# Solar_LEDs.net
KiCad netlist of a schematic drawn in EAGLE
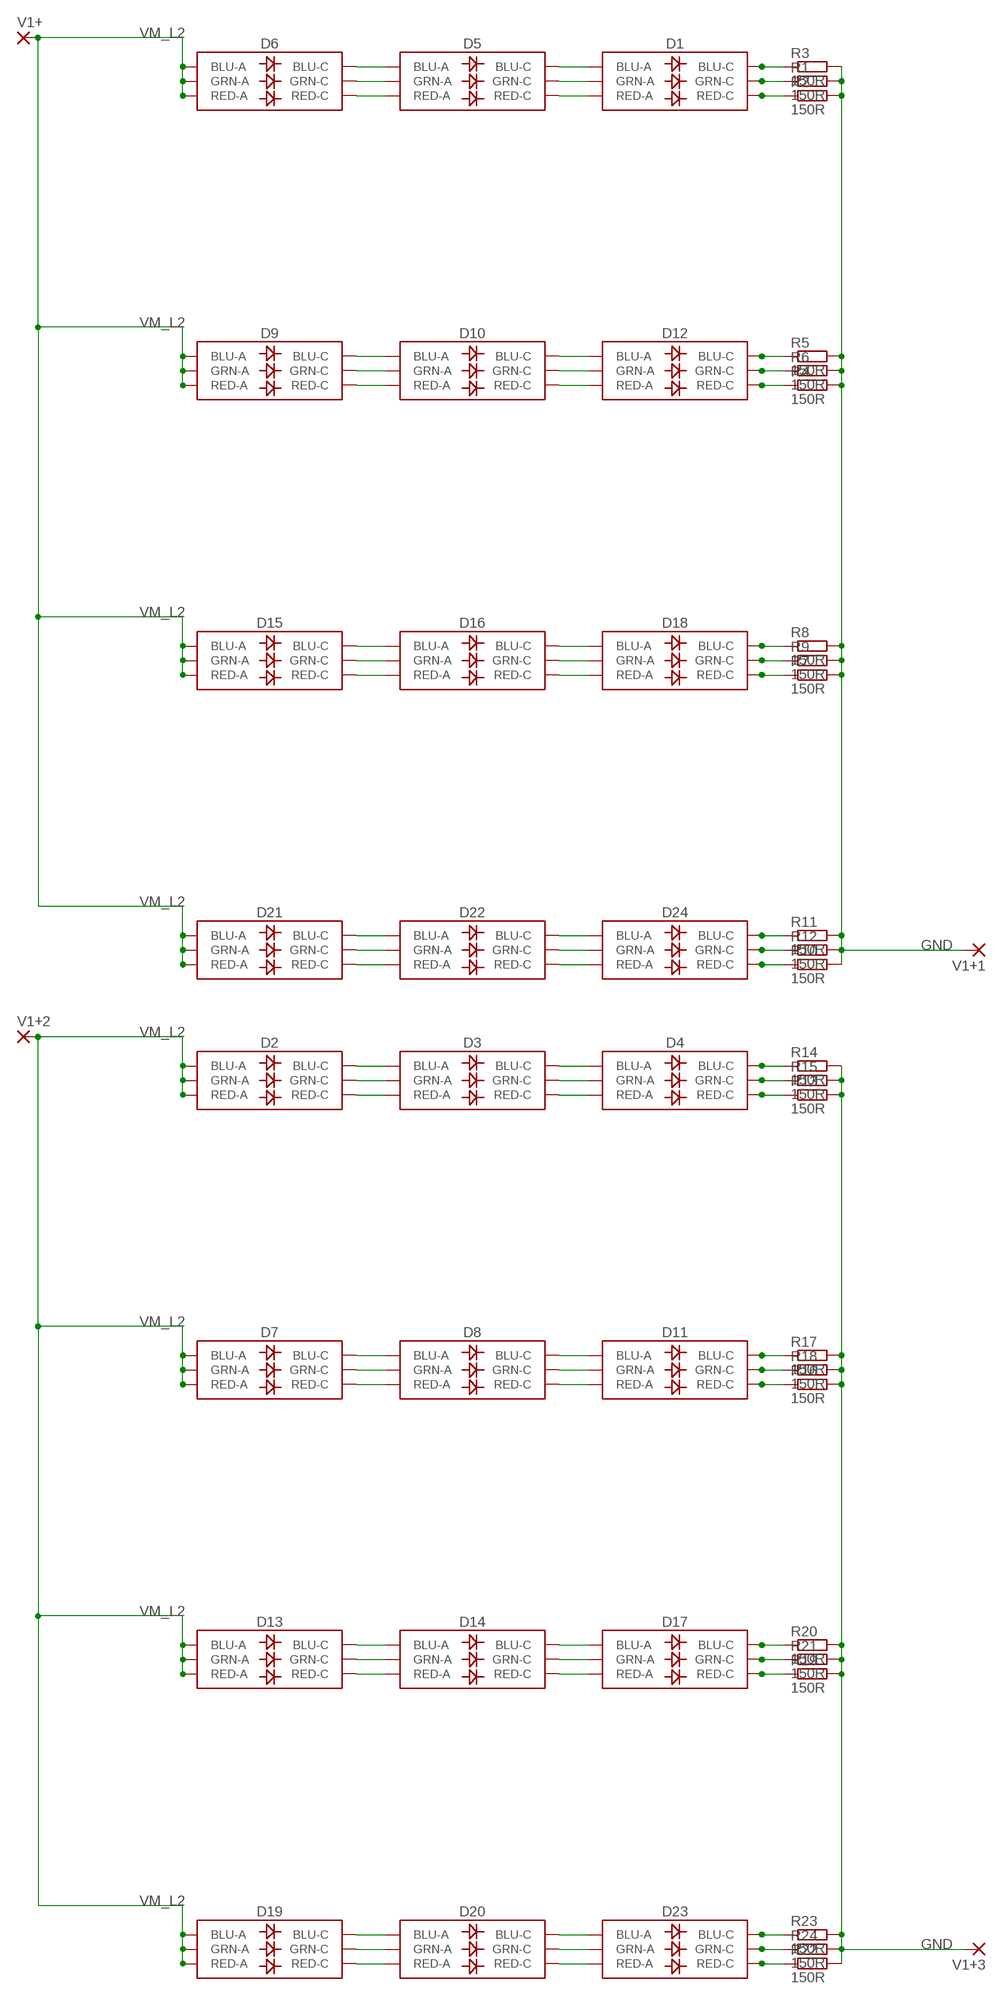
[diagram p0: schematic, sheet 1]

(export (version "E")
  (design (tool "Eeschema 10.0.6"))
  (components
    (comp (ref "D1")
      (value "LED-RGBNO_IC")
      (footprint "eagle-import:LED-TRICOLOR-5050")
      (libsource (lib "eagle-import") (part "LED-RGBNO_IC"))
    )
    (comp (ref "D2")
      (value "LED-RGBNO_IC")
      (footprint "eagle-import:LED-TRICOLOR-5050")
      (libsource (lib "eagle-import") (part "LED-RGBNO_IC"))
    )
    (comp (ref "D3")
      (value "LED-RGBNO_IC")
      (footprint "eagle-import:LED-TRICOLOR-5050")
      (libsource (lib "eagle-import") (part "LED-RGBNO_IC"))
    )
    (comp (ref "D4")
      (value "LED-RGBNO_IC")
      (footprint "eagle-import:LED-TRICOLOR-5050")
      (libsource (lib "eagle-import") (part "LED-RGBNO_IC"))
    )
    (comp (ref "D5")
      (value "LED-RGBNO_IC")
      (footprint "eagle-import:LED-TRICOLOR-5050")
      (libsource (lib "eagle-import") (part "LED-RGBNO_IC"))
    )
    (comp (ref "D6")
      (value "LED-RGBNO_IC")
      (footprint "eagle-import:LED-TRICOLOR-5050")
      (libsource (lib "eagle-import") (part "LED-RGBNO_IC"))
    )
    (comp (ref "D7")
      (value "LED-RGBNO_IC")
      (footprint "eagle-import:LED-TRICOLOR-5050")
      (libsource (lib "eagle-import") (part "LED-RGBNO_IC"))
    )
    (comp (ref "D8")
      (value "LED-RGBNO_IC")
      (footprint "eagle-import:LED-TRICOLOR-5050")
      (libsource (lib "eagle-import") (part "LED-RGBNO_IC"))
    )
    (comp (ref "D9")
      (value "LED-RGBNO_IC")
      (footprint "eagle-import:LED-TRICOLOR-5050")
      (libsource (lib "eagle-import") (part "LED-RGBNO_IC"))
    )
    (comp (ref "D10")
      (value "LED-RGBNO_IC")
      (footprint "eagle-import:LED-TRICOLOR-5050")
      (libsource (lib "eagle-import") (part "LED-RGBNO_IC"))
    )
    (comp (ref "D11")
      (value "LED-RGBNO_IC")
      (footprint "eagle-import:LED-TRICOLOR-5050")
      (libsource (lib "eagle-import") (part "LED-RGBNO_IC"))
    )
    (comp (ref "D12")
      (value "LED-RGBNO_IC")
      (footprint "eagle-import:LED-TRICOLOR-5050")
      (libsource (lib "eagle-import") (part "LED-RGBNO_IC"))
    )
    (comp (ref "D13")
      (value "LED-RGBNO_IC")
      (footprint "eagle-import:LED-TRICOLOR-5050")
      (libsource (lib "eagle-import") (part "LED-RGBNO_IC"))
    )
    (comp (ref "D14")
      (value "LED-RGBNO_IC")
      (footprint "eagle-import:LED-TRICOLOR-5050")
      (libsource (lib "eagle-import") (part "LED-RGBNO_IC"))
    )
    (comp (ref "D15")
      (value "LED-RGBNO_IC")
      (footprint "eagle-import:LED-TRICOLOR-5050")
      (libsource (lib "eagle-import") (part "LED-RGBNO_IC"))
    )
    (comp (ref "D16")
      (value "LED-RGBNO_IC")
      (footprint "eagle-import:LED-TRICOLOR-5050")
      (libsource (lib "eagle-import") (part "LED-RGBNO_IC"))
    )
    (comp (ref "D17")
      (value "LED-RGBNO_IC")
      (footprint "eagle-import:LED-TRICOLOR-5050")
      (libsource (lib "eagle-import") (part "LED-RGBNO_IC"))
    )
    (comp (ref "D18")
      (value "LED-RGBNO_IC")
      (footprint "eagle-import:LED-TRICOLOR-5050")
      (libsource (lib "eagle-import") (part "LED-RGBNO_IC"))
    )
    (comp (ref "D19")
      (value "LED-RGBNO_IC")
      (footprint "eagle-import:LED-TRICOLOR-5050")
      (libsource (lib "eagle-import") (part "LED-RGBNO_IC"))
    )
    (comp (ref "D20")
      (value "LED-RGBNO_IC")
      (footprint "eagle-import:LED-TRICOLOR-5050")
      (libsource (lib "eagle-import") (part "LED-RGBNO_IC"))
    )
    (comp (ref "D21")
      (value "LED-RGBNO_IC")
      (footprint "eagle-import:LED-TRICOLOR-5050")
      (libsource (lib "eagle-import") (part "LED-RGBNO_IC"))
    )
    (comp (ref "D22")
      (value "LED-RGBNO_IC")
      (footprint "eagle-import:LED-TRICOLOR-5050")
      (libsource (lib "eagle-import") (part "LED-RGBNO_IC"))
    )
    (comp (ref "D23")
      (value "LED-RGBNO_IC")
      (footprint "eagle-import:LED-TRICOLOR-5050")
      (libsource (lib "eagle-import") (part "LED-RGBNO_IC"))
    )
    (comp (ref "D24")
      (value "LED-RGBNO_IC")
      (footprint "eagle-import:LED-TRICOLOR-5050")
      (libsource (lib "eagle-import") (part "LED-RGBNO_IC"))
    )
    (comp (ref "R1")
      (value "150R")
      (footprint "eagle-import:M1206")
      (libsource (lib "eagle-import") (part "R-EU_M1206"))
    )
    (comp (ref "R2")
      (value "150R")
      (footprint "eagle-import:M1206")
      (libsource (lib "eagle-import") (part "R-EU_M1206"))
    )
    (comp (ref "R3")
      (value "150R")
      (footprint "eagle-import:M1206")
      (libsource (lib "eagle-import") (part "R-EU_M1206"))
    )
    (comp (ref "R4")
      (value "150R")
      (footprint "eagle-import:M1206")
      (libsource (lib "eagle-import") (part "R-EU_M1206"))
    )
    (comp (ref "R5")
      (value "150R")
      (footprint "eagle-import:M1206")
      (libsource (lib "eagle-import") (part "R-EU_M1206"))
    )
    (comp (ref "R6")
      (value "150R")
      (footprint "eagle-import:M1206")
      (libsource (lib "eagle-import") (part "R-EU_M1206"))
    )
    (comp (ref "R7")
      (value "150R")
      (footprint "eagle-import:M1206")
      (libsource (lib "eagle-import") (part "R-EU_M1206"))
    )
    (comp (ref "R8")
      (value "150R")
      (footprint "eagle-import:M1206")
      (libsource (lib "eagle-import") (part "R-EU_M1206"))
    )
    (comp (ref "R9")
      (value "150R")
      (footprint "eagle-import:M1206")
      (libsource (lib "eagle-import") (part "R-EU_M1206"))
    )
    (comp (ref "R10")
      (value "150R")
      (footprint "eagle-import:M1206")
      (libsource (lib "eagle-import") (part "R-EU_M1206"))
    )
    (comp (ref "R11")
      (value "150R")
      (footprint "eagle-import:M1206")
      (libsource (lib "eagle-import") (part "R-EU_M1206"))
    )
    (comp (ref "R12")
      (value "150R")
      (footprint "eagle-import:M1206")
      (libsource (lib "eagle-import") (part "R-EU_M1206"))
    )
    (comp (ref "R13")
      (value "150R")
      (footprint "eagle-import:M1206")
      (libsource (lib "eagle-import") (part "R-EU_M1206"))
    )
    (comp (ref "R14")
      (value "150R")
      (footprint "eagle-import:M1206")
      (libsource (lib "eagle-import") (part "R-EU_M1206"))
    )
    (comp (ref "R15")
      (value "150R")
      (footprint "eagle-import:M1206")
      (libsource (lib "eagle-import") (part "R-EU_M1206"))
    )
    (comp (ref "R16")
      (value "150R")
      (footprint "eagle-import:M1206")
      (libsource (lib "eagle-import") (part "R-EU_M1206"))
    )
    (comp (ref "R17")
      (value "150R")
      (footprint "eagle-import:M1206")
      (libsource (lib "eagle-import") (part "R-EU_M1206"))
    )
    (comp (ref "R18")
      (value "150R")
      (footprint "eagle-import:M1206")
      (libsource (lib "eagle-import") (part "R-EU_M1206"))
    )
    (comp (ref "R19")
      (value "150R")
      (footprint "eagle-import:M1206")
      (libsource (lib "eagle-import") (part "R-EU_M1206"))
    )
    (comp (ref "R20")
      (value "150R")
      (footprint "eagle-import:M1206")
      (libsource (lib "eagle-import") (part "R-EU_M1206"))
    )
    (comp (ref "R21")
      (value "150R")
      (footprint "eagle-import:M1206")
      (libsource (lib "eagle-import") (part "R-EU_M1206"))
    )
    (comp (ref "R22")
      (value "150R")
      (footprint "eagle-import:M1206")
      (libsource (lib "eagle-import") (part "R-EU_M1206"))
    )
    (comp (ref "R23")
      (value "150R")
      (footprint "eagle-import:M1206")
      (libsource (lib "eagle-import") (part "R-EU_M1206"))
    )
    (comp (ref "R24")
      (value "150R")
      (footprint "eagle-import:M1206")
      (libsource (lib "eagle-import") (part "R-EU_M1206"))
    )
    (comp (ref "V1+")
      (value "2,54/1,0")
      (footprint "eagle-import:2,54_1,0")
      (libsource (lib "eagle-import") (part "2,54/1,0"))
    )
    (comp (ref "V1+1")
      (value "2,54/1,0")
      (footprint "eagle-import:2,54_1,0")
      (libsource (lib "eagle-import") (part "2,54/1,0"))
    )
    (comp (ref "V1+2")
      (value "2,54/1,0")
      (footprint "eagle-import:2,54_1,0")
      (libsource (lib "eagle-import") (part "2,54/1,0"))
    )
    (comp (ref "V1+3")
      (value "2,54/1,0")
      (footprint "eagle-import:2,54_1,0")
      (libsource (lib "eagle-import") (part "2,54/1,0"))
    )
  )
  (nets
    (net (code "1") (name "/GND") (class "Default")
      (node (ref "R1") (pin "2") (pinfunction "2_2") (pintype "passive"))
      (node (ref "R10") (pin "2") (pinfunction "2_2") (pintype "passive"))
      (node (ref "R11") (pin "2") (pinfunction "2_2") (pintype "passive"))
      (node (ref "R12") (pin "2") (pinfunction "2_2") (pintype "passive"))
      (node (ref "R13") (pin "2") (pinfunction "2_2") (pintype "passive"))
      (node (ref "R14") (pin "2") (pinfunction "2_2") (pintype "passive"))
      (node (ref "R15") (pin "2") (pinfunction "2_2") (pintype "passive"))
      (node (ref "R16") (pin "2") (pinfunction "2_2") (pintype "passive"))
      (node (ref "R17") (pin "2") (pinfunction "2_2") (pintype "passive"))
      (node (ref "R18") (pin "2") (pinfunction "2_2") (pintype "passive"))
      (node (ref "R19") (pin "2") (pinfunction "2_2") (pintype "passive"))
      (node (ref "R2") (pin "2") (pinfunction "2_2") (pintype "passive"))
      (node (ref "R20") (pin "2") (pinfunction "2_2") (pintype "passive"))
      (node (ref "R21") (pin "2") (pinfunction "2_2") (pintype "passive"))
      (node (ref "R22") (pin "2") (pinfunction "2_2") (pintype "passive"))
      (node (ref "R23") (pin "2") (pinfunction "2_2") (pintype "passive"))
      (node (ref "R24") (pin "2") (pinfunction "2_2") (pintype "passive"))
      (node (ref "R3") (pin "2") (pinfunction "2_2") (pintype "passive"))
      (node (ref "R4") (pin "2") (pinfunction "2_2") (pintype "passive"))
      (node (ref "R5") (pin "2") (pinfunction "2_2") (pintype "passive"))
      (node (ref "R6") (pin "2") (pinfunction "2_2") (pintype "passive"))
      (node (ref "R7") (pin "2") (pinfunction "2_2") (pintype "passive"))
      (node (ref "R8") (pin "2") (pinfunction "2_2") (pintype "passive"))
      (node (ref "R9") (pin "2") (pinfunction "2_2") (pintype "passive"))
      (node (ref "V1+1") (pin "1") (pinfunction "P_1") (pintype "passive"))
      (node (ref "V1+3") (pin "1") (pinfunction "P_1") (pintype "passive"))
    )
    (net (code "2") (name "/VM_L2") (class "Default")
      (node (ref "D13") (pin "1") (pinfunction "GRN-A_1") (pintype "bidirectional"))
      (node (ref "D13") (pin "2") (pinfunction "RED-A_2") (pintype "bidirectional"))
      (node (ref "D13") (pin "3") (pinfunction "BLU-A_3") (pintype "bidirectional"))
      (node (ref "D15") (pin "1") (pinfunction "GRN-A_1") (pintype "bidirectional"))
      (node (ref "D15") (pin "2") (pinfunction "RED-A_2") (pintype "bidirectional"))
      (node (ref "D15") (pin "3") (pinfunction "BLU-A_3") (pintype "bidirectional"))
      (node (ref "D19") (pin "1") (pinfunction "GRN-A_1") (pintype "bidirectional"))
      (node (ref "D19") (pin "2") (pinfunction "RED-A_2") (pintype "bidirectional"))
      (node (ref "D19") (pin "3") (pinfunction "BLU-A_3") (pintype "bidirectional"))
      (node (ref "D2") (pin "1") (pinfunction "GRN-A_1") (pintype "bidirectional"))
      (node (ref "D2") (pin "2") (pinfunction "RED-A_2") (pintype "bidirectional"))
      (node (ref "D2") (pin "3") (pinfunction "BLU-A_3") (pintype "bidirectional"))
      (node (ref "D21") (pin "1") (pinfunction "GRN-A_1") (pintype "bidirectional"))
      (node (ref "D21") (pin "2") (pinfunction "RED-A_2") (pintype "bidirectional"))
      (node (ref "D21") (pin "3") (pinfunction "BLU-A_3") (pintype "bidirectional"))
      (node (ref "D6") (pin "1") (pinfunction "GRN-A_1") (pintype "bidirectional"))
      (node (ref "D6") (pin "2") (pinfunction "RED-A_2") (pintype "bidirectional"))
      (node (ref "D6") (pin "3") (pinfunction "BLU-A_3") (pintype "bidirectional"))
      (node (ref "D7") (pin "1") (pinfunction "GRN-A_1") (pintype "bidirectional"))
      (node (ref "D7") (pin "2") (pinfunction "RED-A_2") (pintype "bidirectional"))
      (node (ref "D7") (pin "3") (pinfunction "BLU-A_3") (pintype "bidirectional"))
      (node (ref "D9") (pin "1") (pinfunction "GRN-A_1") (pintype "bidirectional"))
      (node (ref "D9") (pin "2") (pinfunction "RED-A_2") (pintype "bidirectional"))
      (node (ref "D9") (pin "3") (pinfunction "BLU-A_3") (pintype "bidirectional"))
      (node (ref "V1+") (pin "1") (pinfunction "P_1") (pintype "passive"))
      (node (ref "V1+2") (pin "1") (pinfunction "P_1") (pintype "passive"))
    )
    (net (code "3") (name "Net-(D1-BLU-A)") (class "Default")
      (node (ref "D1") (pin "3") (pinfunction "BLU-A_3") (pintype "bidirectional"))
      (node (ref "D5") (pin "4") (pinfunction "BLU-C_4") (pintype "bidirectional"))
    )
    (net (code "4") (name "Net-(D1-BLU-C)") (class "Default")
      (node (ref "D1") (pin "4") (pinfunction "BLU-C_4") (pintype "bidirectional"))
      (node (ref "R3") (pin "1") (pinfunction "1_1") (pintype "passive"))
    )
    (net (code "5") (name "Net-(D1-GRN-A)") (class "Default")
      (node (ref "D1") (pin "1") (pinfunction "GRN-A_1") (pintype "bidirectional"))
      (node (ref "D5") (pin "6") (pinfunction "GRN-C_6") (pintype "bidirectional"))
    )
    (net (code "6") (name "Net-(D1-GRN-C)") (class "Default")
      (node (ref "D1") (pin "6") (pinfunction "GRN-C_6") (pintype "bidirectional"))
      (node (ref "R1") (pin "1") (pinfunction "1_1") (pintype "passive"))
    )
    (net (code "7") (name "Net-(D1-RED-A)") (class "Default")
      (node (ref "D1") (pin "2") (pinfunction "RED-A_2") (pintype "bidirectional"))
      (node (ref "D5") (pin "5") (pinfunction "RED-C_5") (pintype "bidirectional"))
    )
    (net (code "8") (name "Net-(D1-RED-C)") (class "Default")
      (node (ref "D1") (pin "5") (pinfunction "RED-C_5") (pintype "bidirectional"))
      (node (ref "R2") (pin "1") (pinfunction "1_1") (pintype "passive"))
    )
    (net (code "9") (name "Net-(D2-BLU-C)") (class "Default")
      (node (ref "D2") (pin "4") (pinfunction "BLU-C_4") (pintype "bidirectional"))
      (node (ref "D3") (pin "3") (pinfunction "BLU-A_3") (pintype "bidirectional"))
    )
    (net (code "10") (name "Net-(D2-GRN-C)") (class "Default")
      (node (ref "D2") (pin "6") (pinfunction "GRN-C_6") (pintype "bidirectional"))
      (node (ref "D3") (pin "1") (pinfunction "GRN-A_1") (pintype "bidirectional"))
    )
    (net (code "11") (name "Net-(D2-RED-C)") (class "Default")
      (node (ref "D2") (pin "5") (pinfunction "RED-C_5") (pintype "bidirectional"))
      (node (ref "D3") (pin "2") (pinfunction "RED-A_2") (pintype "bidirectional"))
    )
    (net (code "12") (name "Net-(D3-BLU-C)") (class "Default")
      (node (ref "D3") (pin "4") (pinfunction "BLU-C_4") (pintype "bidirectional"))
      (node (ref "D4") (pin "3") (pinfunction "BLU-A_3") (pintype "bidirectional"))
    )
    (net (code "13") (name "Net-(D3-GRN-C)") (class "Default")
      (node (ref "D3") (pin "6") (pinfunction "GRN-C_6") (pintype "bidirectional"))
      (node (ref "D4") (pin "1") (pinfunction "GRN-A_1") (pintype "bidirectional"))
    )
    (net (code "14") (name "Net-(D3-RED-C)") (class "Default")
      (node (ref "D3") (pin "5") (pinfunction "RED-C_5") (pintype "bidirectional"))
      (node (ref "D4") (pin "2") (pinfunction "RED-A_2") (pintype "bidirectional"))
    )
    (net (code "15") (name "Net-(D4-BLU-C)") (class "Default")
      (node (ref "D4") (pin "4") (pinfunction "BLU-C_4") (pintype "bidirectional"))
      (node (ref "R14") (pin "1") (pinfunction "1_1") (pintype "passive"))
    )
    (net (code "16") (name "Net-(D4-GRN-C)") (class "Default")
      (node (ref "D4") (pin "6") (pinfunction "GRN-C_6") (pintype "bidirectional"))
      (node (ref "R15") (pin "1") (pinfunction "1_1") (pintype "passive"))
    )
    (net (code "17") (name "Net-(D4-RED-C)") (class "Default")
      (node (ref "D4") (pin "5") (pinfunction "RED-C_5") (pintype "bidirectional"))
      (node (ref "R13") (pin "1") (pinfunction "1_1") (pintype "passive"))
    )
    (net (code "18") (name "Net-(D5-BLU-A)") (class "Default")
      (node (ref "D5") (pin "3") (pinfunction "BLU-A_3") (pintype "bidirectional"))
      (node (ref "D6") (pin "4") (pinfunction "BLU-C_4") (pintype "bidirectional"))
    )
    (net (code "19") (name "Net-(D5-GRN-A)") (class "Default")
      (node (ref "D5") (pin "1") (pinfunction "GRN-A_1") (pintype "bidirectional"))
      (node (ref "D6") (pin "6") (pinfunction "GRN-C_6") (pintype "bidirectional"))
    )
    (net (code "20") (name "Net-(D5-RED-A)") (class "Default")
      (node (ref "D5") (pin "2") (pinfunction "RED-A_2") (pintype "bidirectional"))
      (node (ref "D6") (pin "5") (pinfunction "RED-C_5") (pintype "bidirectional"))
    )
    (net (code "21") (name "Net-(D7-BLU-C)") (class "Default")
      (node (ref "D7") (pin "4") (pinfunction "BLU-C_4") (pintype "bidirectional"))
      (node (ref "D8") (pin "3") (pinfunction "BLU-A_3") (pintype "bidirectional"))
    )
    (net (code "22") (name "Net-(D7-GRN-C)") (class "Default")
      (node (ref "D7") (pin "6") (pinfunction "GRN-C_6") (pintype "bidirectional"))
      (node (ref "D8") (pin "1") (pinfunction "GRN-A_1") (pintype "bidirectional"))
    )
    (net (code "23") (name "Net-(D7-RED-C)") (class "Default")
      (node (ref "D7") (pin "5") (pinfunction "RED-C_5") (pintype "bidirectional"))
      (node (ref "D8") (pin "2") (pinfunction "RED-A_2") (pintype "bidirectional"))
    )
    (net (code "24") (name "Net-(D10-BLU-A)") (class "Default")
      (node (ref "D10") (pin "3") (pinfunction "BLU-A_3") (pintype "bidirectional"))
      (node (ref "D9") (pin "4") (pinfunction "BLU-C_4") (pintype "bidirectional"))
    )
    (net (code "25") (name "Net-(D10-BLU-C)") (class "Default")
      (node (ref "D10") (pin "4") (pinfunction "BLU-C_4") (pintype "bidirectional"))
      (node (ref "D12") (pin "3") (pinfunction "BLU-A_3") (pintype "bidirectional"))
    )
    (net (code "26") (name "Net-(D10-GRN-A)") (class "Default")
      (node (ref "D10") (pin "1") (pinfunction "GRN-A_1") (pintype "bidirectional"))
      (node (ref "D9") (pin "6") (pinfunction "GRN-C_6") (pintype "bidirectional"))
    )
    (net (code "27") (name "Net-(D10-GRN-C)") (class "Default")
      (node (ref "D10") (pin "6") (pinfunction "GRN-C_6") (pintype "bidirectional"))
      (node (ref "D12") (pin "1") (pinfunction "GRN-A_1") (pintype "bidirectional"))
    )
    (net (code "28") (name "Net-(D10-RED-A)") (class "Default")
      (node (ref "D10") (pin "2") (pinfunction "RED-A_2") (pintype "bidirectional"))
      (node (ref "D9") (pin "5") (pinfunction "RED-C_5") (pintype "bidirectional"))
    )
    (net (code "29") (name "Net-(D10-RED-C)") (class "Default")
      (node (ref "D10") (pin "5") (pinfunction "RED-C_5") (pintype "bidirectional"))
      (node (ref "D12") (pin "2") (pinfunction "RED-A_2") (pintype "bidirectional"))
    )
    (net (code "30") (name "Net-(D11-BLU-A)") (class "Default")
      (node (ref "D11") (pin "3") (pinfunction "BLU-A_3") (pintype "bidirectional"))
      (node (ref "D8") (pin "4") (pinfunction "BLU-C_4") (pintype "bidirectional"))
    )
    (net (code "31") (name "Net-(D11-BLU-C)") (class "Default")
      (node (ref "D11") (pin "4") (pinfunction "BLU-C_4") (pintype "bidirectional"))
      (node (ref "R17") (pin "1") (pinfunction "1_1") (pintype "passive"))
    )
    (net (code "32") (name "Net-(D11-GRN-A)") (class "Default")
      (node (ref "D11") (pin "1") (pinfunction "GRN-A_1") (pintype "bidirectional"))
      (node (ref "D8") (pin "6") (pinfunction "GRN-C_6") (pintype "bidirectional"))
    )
    (net (code "33") (name "Net-(D11-GRN-C)") (class "Default")
      (node (ref "D11") (pin "6") (pinfunction "GRN-C_6") (pintype "bidirectional"))
      (node (ref "R18") (pin "1") (pinfunction "1_1") (pintype "passive"))
    )
    (net (code "34") (name "Net-(D11-RED-A)") (class "Default")
      (node (ref "D11") (pin "2") (pinfunction "RED-A_2") (pintype "bidirectional"))
      (node (ref "D8") (pin "5") (pinfunction "RED-C_5") (pintype "bidirectional"))
    )
    (net (code "35") (name "Net-(D11-RED-C)") (class "Default")
      (node (ref "D11") (pin "5") (pinfunction "RED-C_5") (pintype "bidirectional"))
      (node (ref "R16") (pin "1") (pinfunction "1_1") (pintype "passive"))
    )
    (net (code "36") (name "Net-(D12-BLU-C)") (class "Default")
      (node (ref "D12") (pin "4") (pinfunction "BLU-C_4") (pintype "bidirectional"))
      (node (ref "R5") (pin "1") (pinfunction "1_1") (pintype "passive"))
    )
    (net (code "37") (name "Net-(D12-GRN-C)") (class "Default")
      (node (ref "D12") (pin "6") (pinfunction "GRN-C_6") (pintype "bidirectional"))
      (node (ref "R6") (pin "1") (pinfunction "1_1") (pintype "passive"))
    )
    (net (code "38") (name "Net-(D12-RED-C)") (class "Default")
      (node (ref "D12") (pin "5") (pinfunction "RED-C_5") (pintype "bidirectional"))
      (node (ref "R4") (pin "1") (pinfunction "1_1") (pintype "passive"))
    )
    (net (code "39") (name "Net-(D13-BLU-C)") (class "Default")
      (node (ref "D13") (pin "4") (pinfunction "BLU-C_4") (pintype "bidirectional"))
      (node (ref "D14") (pin "3") (pinfunction "BLU-A_3") (pintype "bidirectional"))
    )
    (net (code "40") (name "Net-(D13-GRN-C)") (class "Default")
      (node (ref "D13") (pin "6") (pinfunction "GRN-C_6") (pintype "bidirectional"))
      (node (ref "D14") (pin "1") (pinfunction "GRN-A_1") (pintype "bidirectional"))
    )
    (net (code "41") (name "Net-(D13-RED-C)") (class "Default")
      (node (ref "D13") (pin "5") (pinfunction "RED-C_5") (pintype "bidirectional"))
      (node (ref "D14") (pin "2") (pinfunction "RED-A_2") (pintype "bidirectional"))
    )
    (net (code "42") (name "Net-(D14-BLU-C)") (class "Default")
      (node (ref "D14") (pin "4") (pinfunction "BLU-C_4") (pintype "bidirectional"))
      (node (ref "D17") (pin "3") (pinfunction "BLU-A_3") (pintype "bidirectional"))
    )
    (net (code "43") (name "Net-(D14-GRN-C)") (class "Default")
      (node (ref "D14") (pin "6") (pinfunction "GRN-C_6") (pintype "bidirectional"))
      (node (ref "D17") (pin "1") (pinfunction "GRN-A_1") (pintype "bidirectional"))
    )
    (net (code "44") (name "Net-(D14-RED-C)") (class "Default")
      (node (ref "D14") (pin "5") (pinfunction "RED-C_5") (pintype "bidirectional"))
      (node (ref "D17") (pin "2") (pinfunction "RED-A_2") (pintype "bidirectional"))
    )
    (net (code "45") (name "Net-(D15-BLU-C)") (class "Default")
      (node (ref "D15") (pin "4") (pinfunction "BLU-C_4") (pintype "bidirectional"))
      (node (ref "D16") (pin "3") (pinfunction "BLU-A_3") (pintype "bidirectional"))
    )
    (net (code "46") (name "Net-(D15-GRN-C)") (class "Default")
      (node (ref "D15") (pin "6") (pinfunction "GRN-C_6") (pintype "bidirectional"))
      (node (ref "D16") (pin "1") (pinfunction "GRN-A_1") (pintype "bidirectional"))
    )
    (net (code "47") (name "Net-(D15-RED-C)") (class "Default")
      (node (ref "D15") (pin "5") (pinfunction "RED-C_5") (pintype "bidirectional"))
      (node (ref "D16") (pin "2") (pinfunction "RED-A_2") (pintype "bidirectional"))
    )
    (net (code "48") (name "Net-(D16-BLU-C)") (class "Default")
      (node (ref "D16") (pin "4") (pinfunction "BLU-C_4") (pintype "bidirectional"))
      (node (ref "D18") (pin "3") (pinfunction "BLU-A_3") (pintype "bidirectional"))
    )
    (net (code "49") (name "Net-(D16-GRN-C)") (class "Default")
      (node (ref "D16") (pin "6") (pinfunction "GRN-C_6") (pintype "bidirectional"))
      (node (ref "D18") (pin "1") (pinfunction "GRN-A_1") (pintype "bidirectional"))
    )
    (net (code "50") (name "Net-(D16-RED-C)") (class "Default")
      (node (ref "D16") (pin "5") (pinfunction "RED-C_5") (pintype "bidirectional"))
      (node (ref "D18") (pin "2") (pinfunction "RED-A_2") (pintype "bidirectional"))
    )
    (net (code "51") (name "Net-(D17-BLU-C)") (class "Default")
      (node (ref "D17") (pin "4") (pinfunction "BLU-C_4") (pintype "bidirectional"))
      (node (ref "R20") (pin "1") (pinfunction "1_1") (pintype "passive"))
    )
    (net (code "52") (name "Net-(D17-GRN-C)") (class "Default")
      (node (ref "D17") (pin "6") (pinfunction "GRN-C_6") (pintype "bidirectional"))
      (node (ref "R21") (pin "1") (pinfunction "1_1") (pintype "passive"))
    )
    (net (code "53") (name "Net-(D17-RED-C)") (class "Default")
      (node (ref "D17") (pin "5") (pinfunction "RED-C_5") (pintype "bidirectional"))
      (node (ref "R19") (pin "1") (pinfunction "1_1") (pintype "passive"))
    )
    (net (code "54") (name "Net-(D18-BLU-C)") (class "Default")
      (node (ref "D18") (pin "4") (pinfunction "BLU-C_4") (pintype "bidirectional"))
      (node (ref "R8") (pin "1") (pinfunction "1_1") (pintype "passive"))
    )
    (net (code "55") (name "Net-(D18-GRN-C)") (class "Default")
      (node (ref "D18") (pin "6") (pinfunction "GRN-C_6") (pintype "bidirectional"))
      (node (ref "R9") (pin "1") (pinfunction "1_1") (pintype "passive"))
    )
    (net (code "56") (name "Net-(D18-RED-C)") (class "Default")
      (node (ref "D18") (pin "5") (pinfunction "RED-C_5") (pintype "bidirectional"))
      (node (ref "R7") (pin "1") (pinfunction "1_1") (pintype "passive"))
    )
    (net (code "57") (name "Net-(D19-BLU-C)") (class "Default")
      (node (ref "D19") (pin "4") (pinfunction "BLU-C_4") (pintype "bidirectional"))
      (node (ref "D20") (pin "3") (pinfunction "BLU-A_3") (pintype "bidirectional"))
    )
    (net (code "58") (name "Net-(D19-GRN-C)") (class "Default")
      (node (ref "D19") (pin "6") (pinfunction "GRN-C_6") (pintype "bidirectional"))
      (node (ref "D20") (pin "1") (pinfunction "GRN-A_1") (pintype "bidirectional"))
    )
    (net (code "59") (name "Net-(D19-RED-C)") (class "Default")
      (node (ref "D19") (pin "5") (pinfunction "RED-C_5") (pintype "bidirectional"))
      (node (ref "D20") (pin "2") (pinfunction "RED-A_2") (pintype "bidirectional"))
    )
    (net (code "60") (name "Net-(D20-BLU-C)") (class "Default")
      (node (ref "D20") (pin "4") (pinfunction "BLU-C_4") (pintype "bidirectional"))
      (node (ref "D23") (pin "3") (pinfunction "BLU-A_3") (pintype "bidirectional"))
    )
    (net (code "61") (name "Net-(D20-GRN-C)") (class "Default")
      (node (ref "D20") (pin "6") (pinfunction "GRN-C_6") (pintype "bidirectional"))
      (node (ref "D23") (pin "1") (pinfunction "GRN-A_1") (pintype "bidirectional"))
    )
    (net (code "62") (name "Net-(D20-RED-C)") (class "Default")
      (node (ref "D20") (pin "5") (pinfunction "RED-C_5") (pintype "bidirectional"))
      (node (ref "D23") (pin "2") (pinfunction "RED-A_2") (pintype "bidirectional"))
    )
    (net (code "63") (name "Net-(D21-BLU-C)") (class "Default")
      (node (ref "D21") (pin "4") (pinfunction "BLU-C_4") (pintype "bidirectional"))
      (node (ref "D22") (pin "3") (pinfunction "BLU-A_3") (pintype "bidirectional"))
    )
    (net (code "64") (name "Net-(D21-GRN-C)") (class "Default")
      (node (ref "D21") (pin "6") (pinfunction "GRN-C_6") (pintype "bidirectional"))
      (node (ref "D22") (pin "1") (pinfunction "GRN-A_1") (pintype "bidirectional"))
    )
    (net (code "65") (name "Net-(D21-RED-C)") (class "Default")
      (node (ref "D21") (pin "5") (pinfunction "RED-C_5") (pintype "bidirectional"))
      (node (ref "D22") (pin "2") (pinfunction "RED-A_2") (pintype "bidirectional"))
    )
    (net (code "66") (name "Net-(D22-BLU-C)") (class "Default")
      (node (ref "D22") (pin "4") (pinfunction "BLU-C_4") (pintype "bidirectional"))
      (node (ref "D24") (pin "3") (pinfunction "BLU-A_3") (pintype "bidirectional"))
    )
    (net (code "67") (name "Net-(D22-GRN-C)") (class "Default")
      (node (ref "D22") (pin "6") (pinfunction "GRN-C_6") (pintype "bidirectional"))
      (node (ref "D24") (pin "1") (pinfunction "GRN-A_1") (pintype "bidirectional"))
    )
    (net (code "68") (name "Net-(D22-RED-C)") (class "Default")
      (node (ref "D22") (pin "5") (pinfunction "RED-C_5") (pintype "bidirectional"))
      (node (ref "D24") (pin "2") (pinfunction "RED-A_2") (pintype "bidirectional"))
    )
    (net (code "69") (name "Net-(D23-BLU-C)") (class "Default")
      (node (ref "D23") (pin "4") (pinfunction "BLU-C_4") (pintype "bidirectional"))
      (node (ref "R23") (pin "1") (pinfunction "1_1") (pintype "passive"))
    )
    (net (code "70") (name "Net-(D23-GRN-C)") (class "Default")
      (node (ref "D23") (pin "6") (pinfunction "GRN-C_6") (pintype "bidirectional"))
      (node (ref "R24") (pin "1") (pinfunction "1_1") (pintype "passive"))
    )
    (net (code "71") (name "Net-(D23-RED-C)") (class "Default")
      (node (ref "D23") (pin "5") (pinfunction "RED-C_5") (pintype "bidirectional"))
      (node (ref "R22") (pin "1") (pinfunction "1_1") (pintype "passive"))
    )
    (net (code "72") (name "Net-(D24-BLU-C)") (class "Default")
      (node (ref "D24") (pin "4") (pinfunction "BLU-C_4") (pintype "bidirectional"))
      (node (ref "R11") (pin "1") (pinfunction "1_1") (pintype "passive"))
    )
    (net (code "73") (name "Net-(D24-GRN-C)") (class "Default")
      (node (ref "D24") (pin "6") (pinfunction "GRN-C_6") (pintype "bidirectional"))
      (node (ref "R12") (pin "1") (pinfunction "1_1") (pintype "passive"))
    )
    (net (code "74") (name "Net-(D24-RED-C)") (class "Default")
      (node (ref "D24") (pin "5") (pinfunction "RED-C_5") (pintype "bidirectional"))
      (node (ref "R10") (pin "1") (pinfunction "1_1") (pintype "passive"))
    )
  )
)
